# Power.net
KiCad netlist of a schematic drawn in Altium Designer
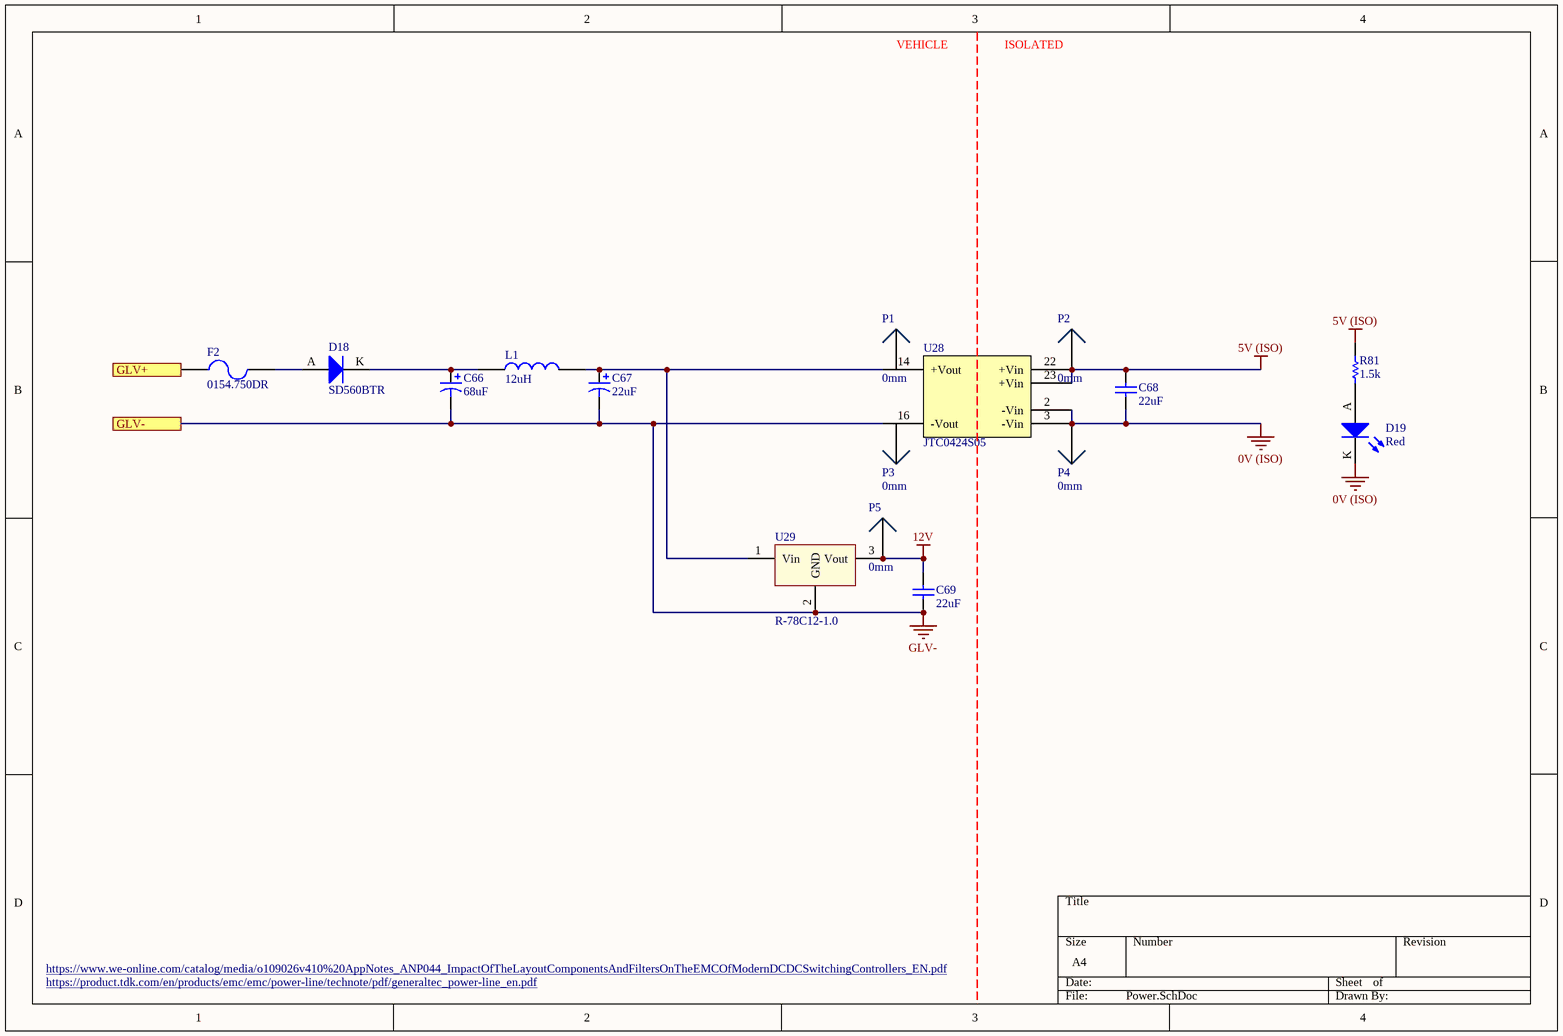
[diagram p0: Power.SchDoc]

(export (version "E")
  (design (tool "Eeschema 10.0.6"))
  (components
    (comp (ref "C66")
      (value "68uF")
      (footprint "2924")
      (fields
        (field (name "PART NUMBER") "TAJV686K035RNJ")
        (field (name "TOLERANCE") "10%")
        (field (name "MANUFACTURER") "AVX Corporation")
      )
      (libsource (lib "ts_20-standard-library") (part "Capacitor (Polarised)"))
    )
    (comp (ref "C67")
      (value "22uF")
      (footprint "2924")
      (fields
        (field (name "PART NUMBER") "TAJV226K050RNJ")
        (field (name "TOLERANCE") "10%")
        (field (name "MANUFACTURER") "AVX Corporation")
      )
      (libsource (lib "ts_20-standard-library") (part "Capacitor (Polarised)"))
    )
    (comp (ref "C68")
      (value "22uF")
      (footprint "1206")
      (fields
        (field (name "PART NUMBER") "CC1206MKX5R7BB226")
        (field (name "TOLERANCE") "20%")
        (field (name "MANUFACTURER") "YAGEO")
      )
      (libsource (lib "ts_20-standard-library") (part "Capacitor"))
    )
    (comp (ref "C69")
      (value "22uF")
      (footprint "1206")
      (fields
        (field (name "PART NUMBER") "CC1206MKX5R7BB226")
        (field (name "TOLERANCE") "20%")
        (field (name "MANUFACTURER") "YAGEO")
      )
      (libsource (lib "ts_20-standard-library") (part "Capacitor"))
    )
    (comp (ref "D18")
      (value "SD560BTR")
      (footprint "SMB Diode")
      (description "1.2V_F 600V 5A SMB")
      (fields
        (field (name "MANUFACTURER") "SMC Diode Solutions")
        (field (name "DIGIKEY PART NUMBER") "1655-1530-2-ND")
      )
      (libsource (lib "ts_20-standard-library") (part "Diode"))
    )
    (comp (ref "D19")
      (value "Red")
      (footprint "0805 LED")
      (description "Red LED Indication - Discrete 1.75V 0805 (2012 Metric)")
      (fields (field (name "PART NUMBER") "SML-210LTT86") (field (name "MANUFACTURER") "ROHM Semiconductor"))
      (libsource (lib "ts_20-standard-library") (part "LED"))
    )
    (comp (ref "F2")
      (value "0154.750DR")
      (footprint "Omni BLOK 0154")
      (description "FUSE BOARD MNT 750MA 125VAC/VDC")
      (fields
        (field (name "MANUFACTURER") "LittelFuse Inc")
        (field (name "DIGIKEY PART NUMBER") "F1221CT-ND")
      )
      (libsource (lib "ts_20-standard-library") (part "Fuse"))
    )
    (comp (ref "L1")
      (value "12uH")
      (footprint "1812")
      (fields
        (field (name "PART NUMBER") "RLS-126")
        (field (name "MANUFACTURER") "Recom")
        (field (name "TOLERANCE") "0.2")
      )
      (libsource (lib "ts_20-standard-library") (part "Inductor"))
    )
    (comp (ref "P1")
      (value "0mm")
      (footprint "TH Test Point")
      (fields (field (name "PART NUMBER") "TH Test Point") (field (name "CONTACT") "NA"))
      (libsource (lib "ts_20-standard-connectors") (part "Test Point"))
    )
    (comp (ref "P2")
      (value "0mm")
      (footprint "TH Test Point")
      (fields (field (name "PART NUMBER") "TH Test Point") (field (name "CONTACT") "NA"))
      (libsource (lib "ts_20-standard-connectors") (part "Test Point"))
    )
    (comp (ref "P3")
      (value "0mm")
      (footprint "TH Test Point")
      (fields (field (name "PART NUMBER") "TH Test Point") (field (name "CONTACT") "NA"))
      (libsource (lib "ts_20-standard-connectors") (part "Test Point"))
    )
    (comp (ref "P4")
      (value "0mm")
      (footprint "TH Test Point")
      (fields (field (name "PART NUMBER") "TH Test Point") (field (name "CONTACT") "NA"))
      (libsource (lib "ts_20-standard-connectors") (part "Test Point"))
    )
    (comp (ref "P5")
      (value "0mm")
      (footprint "TH Test Point")
      (fields (field (name "PART NUMBER") "TH Test Point") (field (name "CONTACT") "NA"))
      (libsource (lib "ts_20-standard-connectors") (part "Test Point"))
    )
    (comp (ref "R81")
      (value "1.5k")
      (footprint "0805")
      (fields
        (field (name "PART NUMBER") "RC0805FR071K5L")
        (field (name "MANUFACTURER") "YAGEO")
        (field (name "TOLERANCE") "0.01")
      )
      (libsource (lib "ts_20-standard-library") (part "Resistor"))
    )
    (comp (ref "U28")
      (value "JTC0424S05")
      (footprint "24-DIP Module, 7 Leads")
      (description "DC DC CONVERTER 5V 4W")
      (fields (field (name "MANUFACTURER") "XP Power") (field (name "DIGIKEY PART NUMBER") "JTC0424S05-ND"))
      (libsource (lib "ts_20-standard-library") (part "JTC0424S05"))
    )
    (comp (ref "U29")
      (value "R-78C12-1.0")
      (footprint "RECOM 3-SIP")
      (description "3PIN DC DC CONVERTER 12V 12W")
      (fields (field (name "MANUFACTURER") "Recom") (field (name "DIGIKEY PART NUMBER") "945-1392-5-ND"))
      (libsource (lib "ts_20-standard-library") (part "R-78C12-1.0"))
    )
  )
  (nets
    (net (code "1") (name "/GLV+") (class "Default")
      (node (ref "F2") (pin "1") (pinfunction "1_1") (pintype "passive"))
    )
    (net (code "2") (name "0V (ISO)") (class "Default")
      (node (ref "C68") (pin "1") (pinfunction "1_1") (pintype "passive"))
      (node (ref "D19") (pin "K") (pinfunction "K_K") (pintype "passive"))
      (node (ref "P4") (pin "1") (pinfunction "1_1") (pintype "passive"))
      (node (ref "U28") (pin "2") (pinfunction "-Vin_2") (pintype "passive"))
      (node (ref "U28") (pin "3") (pinfunction "-Vin_3") (pintype "passive"))
    )
    (net (code "3") (name "5V (ISO)") (class "Default")
      (node (ref "C68") (pin "2") (pinfunction "2_2") (pintype "passive"))
      (node (ref "P2") (pin "1") (pinfunction "1_1") (pintype "passive"))
      (node (ref "R81") (pin "2") (pinfunction "2_2") (pintype "passive"))
      (node (ref "U28") (pin "22") (pinfunction "+Vin_22") (pintype "passive"))
      (node (ref "U28") (pin "23") (pinfunction "+Vin_23") (pintype "passive"))
    )
    (net (code "4") (name "12V") (class "Default")
      (node (ref "C69") (pin "2") (pinfunction "2_2") (pintype "passive"))
      (node (ref "P5") (pin "1") (pinfunction "1_1") (pintype "passive"))
      (node (ref "U29") (pin "3") (pinfunction "Vout_3") (pintype "passive"))
    )
    (net (code "5") (name "GLV-") (class "Default")
      (node (ref "C66") (pin "1") (pinfunction "1_1") (pintype "passive"))
      (node (ref "C67") (pin "1") (pinfunction "1_1") (pintype "passive"))
      (node (ref "C69") (pin "1") (pinfunction "1_1") (pintype "passive"))
      (node (ref "U28") (pin "16") (pinfunction "-Vout_16") (pintype "passive"))
      (node (ref "U29") (pin "2") (pinfunction "GND_2") (pintype "passive"))
    )
    (net (code "6") (name "Net-(C66-Pad2)") (class "Default")
      (node (ref "C66") (pin "2") (pinfunction "2_2") (pintype "passive"))
      (node (ref "D18") (pin "K") (pinfunction "K_K") (pintype "passive"))
      (node (ref "L1") (pin "2") (pinfunction "2_2") (pintype "passive"))
    )
    (net (code "7") (name "Net-(D18-PadA)") (class "Default")
      (node (ref "D18") (pin "A") (pinfunction "A_A") (pintype "passive"))
      (node (ref "F2") (pin "2") (pinfunction "2_2") (pintype "passive"))
    )
    (net (code "8") (name "Net-(D19-PadA)") (class "Default")
      (node (ref "D19") (pin "A") (pinfunction "A_A") (pintype "passive"))
      (node (ref "R81") (pin "1") (pinfunction "1_1") (pintype "passive"))
    )
    (net (code "9") (name "Net-(U28-+Vout)") (class "Default")
      (node (ref "C67") (pin "2") (pinfunction "2_2") (pintype "passive"))
      (node (ref "L1") (pin "1") (pinfunction "1_1") (pintype "passive"))
      (node (ref "U28") (pin "14") (pinfunction "+Vout_14") (pintype "passive"))
      (node (ref "U29") (pin "1") (pinfunction "Vin_1") (pintype "passive"))
    )
    (net (code "10") (name "unconnected-(P1-Pad1)") (class "Default")
      (node (ref "P1") (pin "1") (pinfunction "1_1") (pintype "passive"))
    )
    (net (code "11") (name "unconnected-(P3-Pad1)") (class "Default")
      (node (ref "P3") (pin "1") (pinfunction "1_1") (pintype "passive"))
    )
  )
)
